# PCB.net
KiCad netlist of a schematic drawn in EAGLE
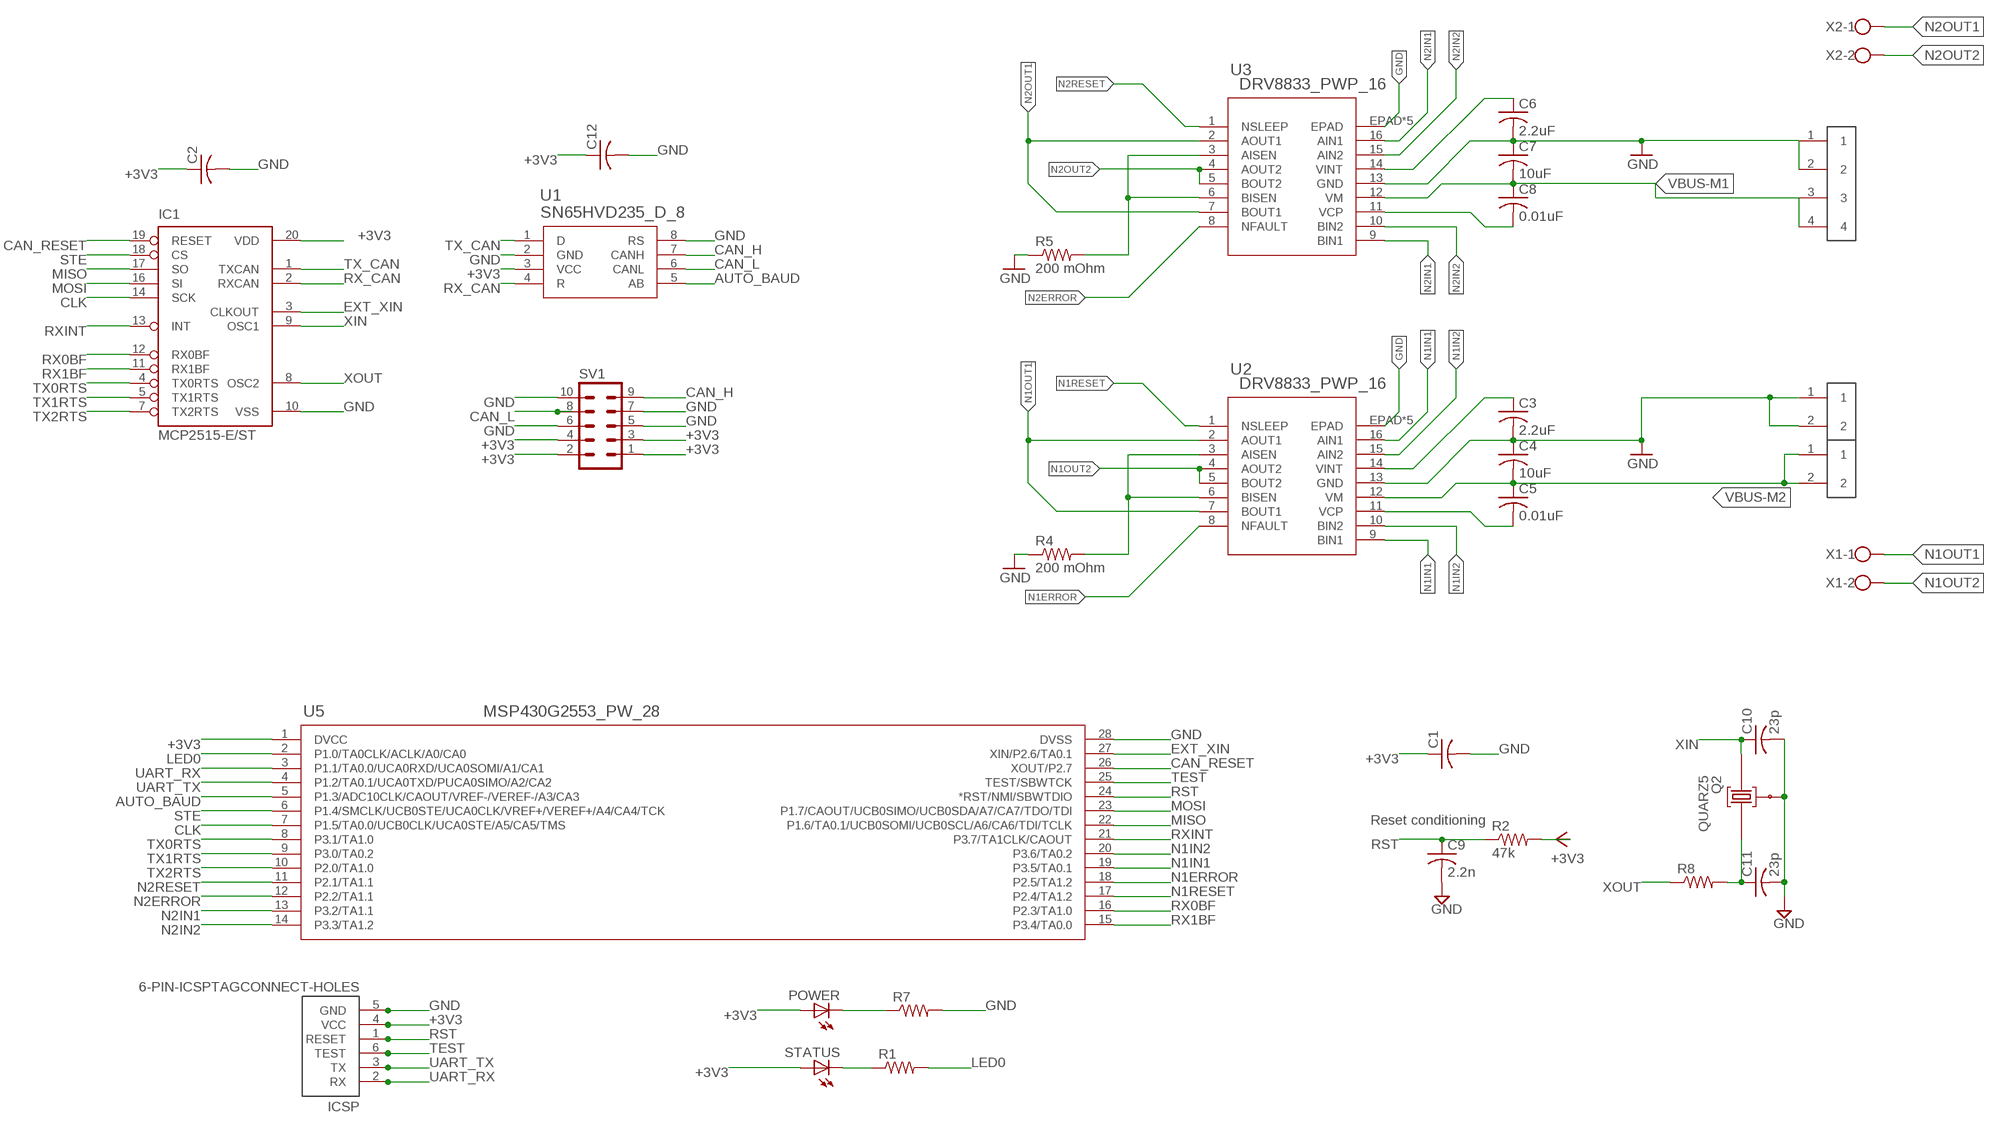
[diagram p0: schematic, sheet 1]

(export (version "E")
  (design (tool "Eeschema 10.0.6"))
  (components
    (comp (ref "C1")
      (value "C-USC0603")
      (footprint "eagle-import:C0603")
      (libsource (lib "eagle-import") (part "C-USC0603"))
    )
    (comp (ref "C2")
      (value "C-USC0603")
      (footprint "eagle-import:C0603")
      (libsource (lib "eagle-import") (part "C-USC0603"))
    )
    (comp (ref "C3")
      (value "2.2uF")
      (footprint "eagle-import:C1206")
      (libsource (lib "eagle-import") (part "C-USC1206"))
    )
    (comp (ref "C4")
      (value "10uF")
      (footprint "eagle-import:C1206")
      (libsource (lib "eagle-import") (part "C-USC1206"))
    )
    (comp (ref "C5")
      (value "0.01uF")
      (footprint "eagle-import:C1206")
      (libsource (lib "eagle-import") (part "C-USC1206"))
    )
    (comp (ref "C6")
      (value "2.2uF")
      (footprint "eagle-import:C1206")
      (libsource (lib "eagle-import") (part "C-USC1206"))
    )
    (comp (ref "C7")
      (value "10uF")
      (footprint "eagle-import:C1206")
      (libsource (lib "eagle-import") (part "C-USC1206"))
    )
    (comp (ref "C8")
      (value "0.01uF")
      (footprint "eagle-import:C1206")
      (libsource (lib "eagle-import") (part "C-USC1206"))
    )
    (comp (ref "C9")
      (value "2.2n")
      (footprint "eagle-import:C0603")
      (libsource (lib "eagle-import") (part "C-USC0603"))
    )
    (comp (ref "C10")
      (value "23p")
      (footprint "eagle-import:C1206")
      (libsource (lib "eagle-import") (part "C-USC1206"))
    )
    (comp (ref "C11")
      (value "23p")
      (footprint "eagle-import:C1206")
      (libsource (lib "eagle-import") (part "C-USC1206"))
    )
    (comp (ref "C12")
      (value "C-USC0603")
      (footprint "eagle-import:C0603")
      (libsource (lib "eagle-import") (part "C-USC0603"))
    )
    (comp (ref "IC1")
      (value "MCP2515-E/ST")
      (footprint "eagle-import:TSSOP20")
      (libsource (lib "eagle-import") (part "MCP2515-E/ST"))
    )
    (comp (ref "ICSP")
      (value "6-PIN-ICSPTAGCONNECT-HOLES")
      (footprint "eagle-import:TAGCONNECT-HOLES")
      (libsource (lib "eagle-import") (part "6-PIN-ICSPTAGCONNECT-HOLES"))
    )
    (comp (ref "POWER")
      (value "LEDCHIP-LED0603")
      (footprint "eagle-import:CHIP-LED0603")
      (libsource (lib "eagle-import") (part "LEDCHIP-LED0603"))
    )
    (comp (ref "Q2")
      (value "QUARZ5")
      (footprint "eagle-import:QUARZ5")
      (libsource (lib "eagle-import") (part "QUARZ5"))
    )
    (comp (ref "R1")
      (value "R-US_R0603")
      (footprint "eagle-import:R0603")
      (libsource (lib "eagle-import") (part "R-US_R0603"))
    )
    (comp (ref "R2")
      (value "47k")
      (footprint "eagle-import:R0603")
      (libsource (lib "eagle-import") (part "R-US_R0603"))
    )
    (comp (ref "R4")
      (value "200 mOhm")
      (footprint "eagle-import:R0805")
      (libsource (lib "eagle-import") (part "R-US_R0805"))
    )
    (comp (ref "R5")
      (value "200 mOhm")
      (footprint "eagle-import:R0805")
      (libsource (lib "eagle-import") (part "R-US_R0805"))
    )
    (comp (ref "R7")
      (value "R-US_R0603")
      (footprint "eagle-import:R0603")
      (libsource (lib "eagle-import") (part "R-US_R0603"))
    )
    (comp (ref "R8")
      (value "R-US_R0603")
      (footprint "eagle-import:R0603")
      (libsource (lib "eagle-import") (part "R-US_R0603"))
    )
    (comp (ref "STATUS")
      (value "LEDCHIP-LED0603")
      (footprint "eagle-import:CHIP-LED0603")
      (libsource (lib "eagle-import") (part "LEDCHIP-LED0603"))
    )
    (comp (ref "SV1")
      (value "MA05-2")
      (footprint "eagle-import:MA05-2")
      (libsource (lib "eagle-import") (part "MA05-2"))
    )
    (comp (ref "U$2")
      (value "1X4_HEADER")
      (footprint "eagle-import:1X4-.1HEADER")
      (libsource (lib "eagle-import") (part "1X4_HEADER"))
    )
    (comp (ref "U$3")
      (value "1X2_HEADER")
      (footprint "eagle-import:1X2-.1HEADER")
      (libsource (lib "eagle-import") (part "1X2_HEADER"))
    )
    (comp (ref "U$4")
      (value "1X2_HEADER")
      (footprint "eagle-import:1X2-.1HEADER")
      (libsource (lib "eagle-import") (part "1X2_HEADER"))
    )
    (comp (ref "U1")
      (value "SN65HVD235_D_8")
      (footprint "eagle-import:D8")
      (fields
        (field (name "GENERIC_PART_NUMBER") "SN65HVD235")
        (field (name "MANUFACTURER") "Texas Instruments")
        (field (name "MANUFACTURER_PART_NUMBER") "sn65hvd235_d_8")
      )
      (libsource (lib "eagle-import") (part "SN65HVD235_D_8"))
    )
    (comp (ref "U2")
      (value "DRV8833_PWP_16")
      (footprint "eagle-import:PWP16_2P31X2P46")
      (fields
        (field (name "GENERIC_PART_NUMBER") "DRV8833")
        (field (name "MANUFACTURER") "Texas Instruments")
        (field (name "MANUFACTURER_PART_NUMBER") "drv8833_pwp_16")
      )
      (libsource (lib "eagle-import") (part "DRV8833_PWP_16"))
    )
    (comp (ref "U3")
      (value "DRV8833_PWP_16")
      (footprint "eagle-import:PWP16_2P31X2P46")
      (fields
        (field (name "GENERIC_PART_NUMBER") "DRV8833")
        (field (name "MANUFACTURER") "Texas Instruments")
        (field (name "MANUFACTURER_PART_NUMBER") "drv8833_pwp_16")
      )
      (libsource (lib "eagle-import") (part "DRV8833_PWP_16"))
    )
    (comp (ref "U5")
      (value "MSP430G2553_PW_28")
      (footprint "eagle-import:PW28")
      (fields
        (field (name "GENERIC_PART_NUMBER") "MSP430G2553")
        (field (name "MANUFACTURER") "Texas Instruments")
        (field (name "MANUFACTURER_PART_NUMBER") "msp430g2553_pw_28")
      )
      (libsource (lib "eagle-import") (part "MSP430G2553_PW_28"))
    )
    (comp (ref "X1")
      (value "W237-102")
      (footprint "eagle-import:W237-102")
      (fields (field (name "MPN") "237-102"))
      (libsource (lib "eagle-import") (part "W237-102"))
    )
    (comp (ref "X2")
      (value "W237-102")
      (footprint "eagle-import:W237-102")
      (fields (field (name "MPN") "237-102"))
      (libsource (lib "eagle-import") (part "W237-102"))
    )
  )
  (nets
    (net (code "1") (name "+3V3") (class "Default")
      (node (ref "C1") (pin "1") (pinfunction "1_1") (pintype "passive"))
      (node (ref "C12") (pin "1") (pinfunction "1_1") (pintype "passive"))
      (node (ref "C2") (pin "1") (pinfunction "1_1") (pintype "passive"))
      (node (ref "IC1") (pin "20") (pinfunction "VDD_20") (pintype "power_in"))
      (node (ref "ICSP") (pin "4") (pinfunction "VCC_4") (pintype "bidirectional"))
      (node (ref "POWER") (pin "A") (pinfunction "A_A") (pintype "passive"))
      (node (ref "R2") (pin "2") (pinfunction "2_2") (pintype "passive"))
      (node (ref "STATUS") (pin "A") (pinfunction "A_A") (pintype "passive"))
      (node (ref "SV1") (pin "1") (pinfunction "1_1") (pintype "passive"))
      (node (ref "SV1") (pin "2") (pinfunction "2_2") (pintype "passive"))
      (node (ref "SV1") (pin "3") (pinfunction "3_3") (pintype "passive"))
      (node (ref "SV1") (pin "4") (pinfunction "4_4") (pintype "passive"))
      (node (ref "U1") (pin "3") (pinfunction "VCC_3") (pintype "power_in"))
      (node (ref "U5") (pin "1") (pinfunction "DVCC_1") (pintype "power_in"))
    )
    (net (code "2") (name "/AUTO_BAUD") (class "Default")
      (node (ref "U1") (pin "5") (pinfunction "AB_5") (pintype "input"))
      (node (ref "U5") (pin "5") (pinfunction "P1.3/ADC10CLK/CAOUT/VREF-/VEREF-/A3/CA3_5") (pintype "bidirectional"))
    )
    (net (code "3") (name "/CAN_H") (class "Default")
      (node (ref "SV1") (pin "9") (pinfunction "9_9") (pintype "passive"))
      (node (ref "U1") (pin "7") (pinfunction "CANH_7") (pintype "output"))
    )
    (net (code "4") (name "/CAN_L") (class "Default")
      (node (ref "SV1") (pin "8") (pinfunction "8_8") (pintype "passive"))
      (node (ref "U1") (pin "6") (pinfunction "CANL_6") (pintype "output"))
    )
    (net (code "5") (name "/CAN_RESET") (class "Default")
      (node (ref "IC1") (pin "19") (pinfunction "RESET_19") (pintype "input"))
      (node (ref "U5") (pin "26") (pinfunction "XOUT/P2.7_26") (pintype "bidirectional"))
    )
    (net (code "6") (name "/CLK") (class "Default")
      (node (ref "IC1") (pin "14") (pinfunction "SCK_14") (pintype "input"))
      (node (ref "U5") (pin "7") (pinfunction "P1.5/TA0.0/UCB0CLK/UCA0STE/A5/CA5/TMS_7") (pintype "bidirectional"))
    )
    (net (code "7") (name "/EXT_XIN") (class "Default")
      (node (ref "IC1") (pin "3") (pinfunction "CLKOUT_3") (pintype "output"))
      (node (ref "U5") (pin "27") (pinfunction "XIN/P2.6/TA0.1_27") (pintype "bidirectional"))
    )
    (net (code "8") (name "/LED0") (class "Default")
      (node (ref "R1") (pin "2") (pinfunction "2_2") (pintype "passive"))
      (node (ref "U5") (pin "2") (pinfunction "P1.0/TA0CLK/ACLK/A0/CA0_2") (pintype "bidirectional"))
    )
    (net (code "9") (name "/MISO") (class "Default")
      (node (ref "IC1") (pin "17") (pinfunction "SO_17") (pintype "output"))
      (node (ref "U5") (pin "22") (pinfunction "P1.6/TA0.1/UCB0SOMI/UCB0SCL/A6/CA6/TDI/TCLK_22") (pintype "bidirectional"))
    )
    (net (code "10") (name "/MOSI") (class "Default")
      (node (ref "IC1") (pin "16") (pinfunction "SI_16") (pintype "input"))
      (node (ref "U5") (pin "23") (pinfunction "P1.7/CAOUT/UCB0SIMO/UCB0SDA/A7/CA7/TDO/TDI_23") (pintype "bidirectional"))
    )
    (net (code "11") (name "/RST") (class "Default")
      (node (ref "C9") (pin "1") (pinfunction "1_1") (pintype "passive"))
      (node (ref "ICSP") (pin "1") (pinfunction "RESET_1") (pintype "bidirectional"))
      (node (ref "R2") (pin "1") (pinfunction "1_1") (pintype "passive"))
      (node (ref "U5") (pin "24") (pinfunction "*RST/NMI/SBWTDIO_24") (pintype "bidirectional"))
    )
    (net (code "12") (name "/RX0BF") (class "Default")
      (node (ref "IC1") (pin "12") (pinfunction "RX0BF_12") (pintype "output"))
      (node (ref "U5") (pin "16") (pinfunction "P2.3/TA1.0_16") (pintype "bidirectional"))
    )
    (net (code "13") (name "/RX1BF") (class "Default")
      (node (ref "IC1") (pin "11") (pinfunction "RX1BF_11") (pintype "output"))
      (node (ref "U5") (pin "15") (pinfunction "P3.4/TA0.0_15") (pintype "bidirectional"))
    )
    (net (code "14") (name "/RXINT") (class "Default")
      (node (ref "IC1") (pin "13") (pinfunction "INT_13") (pintype "output"))
      (node (ref "U5") (pin "21") (pinfunction "P3.7/TA1CLK/CAOUT_21") (pintype "bidirectional"))
    )
    (net (code "15") (name "/RX_CAN") (class "Default")
      (node (ref "IC1") (pin "2") (pinfunction "RXCAN_2") (pintype "input"))
      (node (ref "U1") (pin "4") (pinfunction "R_4") (pintype "input"))
    )
    (net (code "16") (name "/STE") (class "Default")
      (node (ref "IC1") (pin "18") (pinfunction "CS_18") (pintype "input"))
      (node (ref "U5") (pin "6") (pinfunction "P1.4/SMCLK/UCB0STE/UCA0CLK/VREF+/VEREF+/A4/CA4/TCK_6") (pintype "bidirectional"))
    )
    (net (code "17") (name "/TEST") (class "Default")
      (node (ref "ICSP") (pin "6") (pinfunction "TEST_6") (pintype "bidirectional"))
      (node (ref "U5") (pin "25") (pinfunction "TEST/SBWTCK_25") (pintype "bidirectional"))
    )
    (net (code "18") (name "/TX0RTS") (class "Default")
      (node (ref "IC1") (pin "4") (pinfunction "TX0RTS_4") (pintype "input"))
      (node (ref "U5") (pin "8") (pinfunction "P3.1/TA1.0_8") (pintype "bidirectional"))
    )
    (net (code "19") (name "/TX1RTS") (class "Default")
      (node (ref "IC1") (pin "5") (pinfunction "TX1RTS_5") (pintype "input"))
      (node (ref "U5") (pin "9") (pinfunction "P3.0/TA0.2_9") (pintype "bidirectional"))
    )
    (net (code "20") (name "/TX2RTS") (class "Default")
      (node (ref "IC1") (pin "7") (pinfunction "TX2RTS_7") (pintype "input"))
      (node (ref "U5") (pin "10") (pinfunction "P2.0/TA1.0_10") (pintype "bidirectional"))
    )
    (net (code "21") (name "/TX_CAN") (class "Default")
      (node (ref "IC1") (pin "1") (pinfunction "TXCAN_1") (pintype "output"))
      (node (ref "U1") (pin "1") (pinfunction "D_1") (pintype "input"))
    )
    (net (code "22") (name "/UART_RX") (class "Default")
      (node (ref "ICSP") (pin "2") (pinfunction "RX_2") (pintype "bidirectional"))
      (node (ref "U5") (pin "3") (pinfunction "P1.1/TA0.0/UCA0RXD/UCA0SOMI/A1/CA1_3") (pintype "bidirectional"))
    )
    (net (code "23") (name "/UART_TX") (class "Default")
      (node (ref "ICSP") (pin "3") (pinfunction "TX_3") (pintype "bidirectional"))
      (node (ref "U5") (pin "4") (pinfunction "P1.2/TA0.1/UCA0TXD/PUCA0SIMO/A2/CA2_4") (pintype "bidirectional"))
    )
    (net (code "24") (name "/XIN") (class "Default")
      (node (ref "C10") (pin "1") (pinfunction "1_1") (pintype "passive"))
      (node (ref "IC1") (pin "9") (pinfunction "OSC1_9") (pintype "input"))
      (node (ref "Q2") (pin "2") (pinfunction "2_2") (pintype "passive"))
    )
    (net (code "25") (name "/XOUT") (class "Default")
      (node (ref "IC1") (pin "8") (pinfunction "OSC2_8") (pintype "output"))
      (node (ref "R8") (pin "1") (pinfunction "1_1") (pintype "passive"))
    )
    (net (code "26") (name "GND") (class "Default")
      (node (ref "C1") (pin "2") (pinfunction "2_2") (pintype "passive"))
      (node (ref "C10") (pin "2") (pinfunction "2_2") (pintype "passive"))
      (node (ref "C11") (pin "2") (pinfunction "2_2") (pintype "passive"))
      (node (ref "C12") (pin "2") (pinfunction "2_2") (pintype "passive"))
      (node (ref "C2") (pin "2") (pinfunction "2_2") (pintype "passive"))
      (node (ref "C3") (pin "2") (pinfunction "2_2") (pintype "passive"))
      (node (ref "C4") (pin "1") (pinfunction "1_1") (pintype "passive"))
      (node (ref "C6") (pin "2") (pinfunction "2_2") (pintype "passive"))
      (node (ref "C7") (pin "1") (pinfunction "1_1") (pintype "passive"))
      (node (ref "C9") (pin "2") (pinfunction "2_2") (pintype "passive"))
      (node (ref "IC1") (pin "10") (pinfunction "VSS_10") (pintype "power_in"))
      (node (ref "ICSP") (pin "5") (pinfunction "GND_5") (pintype "bidirectional"))
      (node (ref "Q2") (pin "GND@0") (pinfunction "0_GND@0") (pintype "passive"))
      (node (ref "R4") (pin "1") (pinfunction "1_1") (pintype "passive"))
      (node (ref "R5") (pin "1") (pinfunction "1_1") (pintype "passive"))
      (node (ref "R7") (pin "2") (pinfunction "2_2") (pintype "passive"))
      (node (ref "SV1") (pin "10") (pinfunction "10_10") (pintype "passive"))
      (node (ref "SV1") (pin "5") (pinfunction "5_5") (pintype "passive"))
      (node (ref "SV1") (pin "6") (pinfunction "6_6") (pintype "passive"))
      (node (ref "SV1") (pin "7") (pinfunction "7_7") (pintype "passive"))
      (node (ref "U$2") (pin "1") (pinfunction "1_1") (pintype "bidirectional"))
      (node (ref "U$2") (pin "2") (pinfunction "2_2") (pintype "bidirectional"))
      (node (ref "U$3") (pin "1") (pinfunction "1_1") (pintype "bidirectional"))
      (node (ref "U$3") (pin "2") (pinfunction "2_2") (pintype "bidirectional"))
      (node (ref "U1") (pin "2") (pinfunction "GND_2") (pintype "power_in"))
      (node (ref "U1") (pin "8") (pinfunction "RS_8") (pintype "input"))
      (node (ref "U2") (pin "13") (pinfunction "GND_13") (pintype "power_in"))
      (node (ref "U2") (pin "EPAD") (pinfunction "EPAD_EPAD") (pintype "passive"))
      (node (ref "U2") (pin "V") (pinfunction "EPAD_V") (pintype "passive"))
      (node (ref "U2") (pin "V_2") (pinfunction "EPAD_V_2") (pintype "passive"))
      (node (ref "U2") (pin "V_3") (pinfunction "EPAD_V_3") (pintype "passive"))
      (node (ref "U2") (pin "V_6") (pinfunction "EPAD_V_6") (pintype "passive"))
      (node (ref "U3") (pin "13") (pinfunction "GND_13") (pintype "power_in"))
      (node (ref "U3") (pin "EPAD") (pinfunction "EPAD_EPAD") (pintype "passive"))
      (node (ref "U3") (pin "V") (pinfunction "EPAD_V") (pintype "passive"))
      (node (ref "U3") (pin "V_2") (pinfunction "EPAD_V_2") (pintype "passive"))
      (node (ref "U3") (pin "V_3") (pinfunction "EPAD_V_3") (pintype "passive"))
      (node (ref "U3") (pin "V_6") (pinfunction "EPAD_V_6") (pintype "passive"))
      (node (ref "U5") (pin "28") (pinfunction "DVSS_28") (pintype "power_in"))
    )
    (net (code "27") (name "N1ERROR") (class "Default")
      (node (ref "U2") (pin "8") (pinfunction "NFAULT_8") (pintype "output"))
      (node (ref "U5") (pin "18") (pinfunction "P2.5/TA1.2_18") (pintype "bidirectional"))
    )
    (net (code "28") (name "N1IN1") (class "Default")
      (node (ref "U2") (pin "16") (pinfunction "AIN1_16") (pintype "input"))
      (node (ref "U2") (pin "9") (pinfunction "BIN1_9") (pintype "input"))
      (node (ref "U5") (pin "19") (pinfunction "P3.5/TA0.1_19") (pintype "bidirectional"))
    )
    (net (code "29") (name "N1IN2") (class "Default")
      (node (ref "U2") (pin "10") (pinfunction "BIN2_10") (pintype "input"))
      (node (ref "U2") (pin "15") (pinfunction "AIN2_15") (pintype "input"))
      (node (ref "U5") (pin "20") (pinfunction "P3.6/TA0.2_20") (pintype "bidirectional"))
    )
    (net (code "30") (name "N1OUT1") (class "Default")
      (node (ref "U2") (pin "2") (pinfunction "AOUT1_2") (pintype "output"))
      (node (ref "U2") (pin "7") (pinfunction "BOUT1_7") (pintype "output"))
      (node (ref "X1") (pin "1") (pinfunction "KL_1") (pintype "passive"))
    )
    (net (code "31") (name "N1OUT2") (class "Default")
      (node (ref "U2") (pin "4") (pinfunction "AOUT2_4") (pintype "output"))
      (node (ref "U2") (pin "5") (pinfunction "BOUT2_5") (pintype "output"))
      (node (ref "X1") (pin "2") (pinfunction "KL_2") (pintype "passive"))
    )
    (net (code "32") (name "N1RESET") (class "Default")
      (node (ref "U2") (pin "1") (pinfunction "NSLEEP_1") (pintype "input"))
      (node (ref "U5") (pin "17") (pinfunction "P2.4/TA1.2_17") (pintype "bidirectional"))
    )
    (net (code "33") (name "N2ERROR") (class "Default")
      (node (ref "U3") (pin "8") (pinfunction "NFAULT_8") (pintype "output"))
      (node (ref "U5") (pin "12") (pinfunction "P2.2/TA1.1_12") (pintype "bidirectional"))
    )
    (net (code "34") (name "N2IN1") (class "Default")
      (node (ref "U3") (pin "16") (pinfunction "AIN1_16") (pintype "input"))
      (node (ref "U3") (pin "9") (pinfunction "BIN1_9") (pintype "input"))
      (node (ref "U5") (pin "13") (pinfunction "P3.2/TA1.1_13") (pintype "bidirectional"))
    )
    (net (code "35") (name "N2IN2") (class "Default")
      (node (ref "U3") (pin "10") (pinfunction "BIN2_10") (pintype "input"))
      (node (ref "U3") (pin "15") (pinfunction "AIN2_15") (pintype "input"))
      (node (ref "U5") (pin "14") (pinfunction "P3.3/TA1.2_14") (pintype "bidirectional"))
    )
    (net (code "36") (name "N2OUT1") (class "Default")
      (node (ref "U3") (pin "2") (pinfunction "AOUT1_2") (pintype "output"))
      (node (ref "U3") (pin "7") (pinfunction "BOUT1_7") (pintype "output"))
      (node (ref "X2") (pin "1") (pinfunction "KL_1") (pintype "passive"))
    )
    (net (code "37") (name "N2OUT2") (class "Default")
      (node (ref "U3") (pin "4") (pinfunction "AOUT2_4") (pintype "output"))
      (node (ref "U3") (pin "5") (pinfunction "BOUT2_5") (pintype "output"))
      (node (ref "X2") (pin "2") (pinfunction "KL_2") (pintype "passive"))
    )
    (net (code "38") (name "N2RESET") (class "Default")
      (node (ref "U3") (pin "1") (pinfunction "NSLEEP_1") (pintype "input"))
      (node (ref "U5") (pin "11") (pinfunction "P2.1/TA1.1_11") (pintype "bidirectional"))
    )
    (net (code "39") (name "Net-(C11-Pad1)") (class "Default")
      (node (ref "C11") (pin "1") (pinfunction "1_1") (pintype "passive"))
      (node (ref "Q2") (pin "1") (pinfunction "1_1") (pintype "passive"))
      (node (ref "R8") (pin "2") (pinfunction "2_2") (pintype "passive"))
    )
    (net (code "40") (name "Net-(POWER-PadC)") (class "Default")
      (node (ref "POWER") (pin "C") (pinfunction "C_C") (pintype "passive"))
      (node (ref "R7") (pin "1") (pinfunction "1_1") (pintype "passive"))
    )
    (net (code "41") (name "Net-(R1-Pad1)") (class "Default")
      (node (ref "R1") (pin "1") (pinfunction "1_1") (pintype "passive"))
      (node (ref "STATUS") (pin "C") (pinfunction "C_C") (pintype "passive"))
    )
    (net (code "42") (name "Net-(U2-AISEN)") (class "Default")
      (node (ref "R4") (pin "2") (pinfunction "2_2") (pintype "passive"))
      (node (ref "U2") (pin "3") (pinfunction "AISEN_3") (pintype "bidirectional"))
      (node (ref "U2") (pin "6") (pinfunction "BISEN_6") (pintype "bidirectional"))
    )
    (net (code "43") (name "Net-(U2-VCP)") (class "Default")
      (node (ref "C5") (pin "2") (pinfunction "2_2") (pintype "passive"))
      (node (ref "U2") (pin "11") (pinfunction "VCP_11") (pintype "bidirectional"))
    )
    (net (code "44") (name "Net-(U2-VINT)") (class "Default")
      (node (ref "C3") (pin "1") (pinfunction "1_1") (pintype "passive"))
      (node (ref "U2") (pin "14") (pinfunction "VINT_14") (pintype "power_in"))
    )
    (net (code "45") (name "Net-(U3-AISEN)") (class "Default")
      (node (ref "R5") (pin "2") (pinfunction "2_2") (pintype "passive"))
      (node (ref "U3") (pin "3") (pinfunction "AISEN_3") (pintype "bidirectional"))
      (node (ref "U3") (pin "6") (pinfunction "BISEN_6") (pintype "bidirectional"))
    )
    (net (code "46") (name "Net-(U3-VCP)") (class "Default")
      (node (ref "C8") (pin "2") (pinfunction "2_2") (pintype "passive"))
      (node (ref "U3") (pin "11") (pinfunction "VCP_11") (pintype "bidirectional"))
    )
    (net (code "47") (name "Net-(U3-VINT)") (class "Default")
      (node (ref "C6") (pin "1") (pinfunction "1_1") (pintype "passive"))
      (node (ref "U3") (pin "14") (pinfunction "VINT_14") (pintype "power_in"))
    )
    (net (code "48") (name "VBUS-M1") (class "Default")
      (node (ref "C7") (pin "2") (pinfunction "2_2") (pintype "passive"))
      (node (ref "C8") (pin "1") (pinfunction "1_1") (pintype "passive"))
      (node (ref "U$2") (pin "3") (pinfunction "3_3") (pintype "bidirectional"))
      (node (ref "U$2") (pin "4") (pinfunction "4_4") (pintype "bidirectional"))
      (node (ref "U3") (pin "12") (pinfunction "VM_12") (pintype "power_in"))
    )
    (net (code "49") (name "VBUS-M2") (class "Default")
      (node (ref "C4") (pin "2") (pinfunction "2_2") (pintype "passive"))
      (node (ref "C5") (pin "1") (pinfunction "1_1") (pintype "passive"))
      (node (ref "U$4") (pin "1") (pinfunction "1_1") (pintype "bidirectional"))
      (node (ref "U$4") (pin "2") (pinfunction "2_2") (pintype "bidirectional"))
      (node (ref "U2") (pin "12") (pinfunction "VM_12") (pintype "power_in"))
    )
  )
)
